# A-3_sch_class.net
KiCad netlist of a schematic drawn in EAGLE
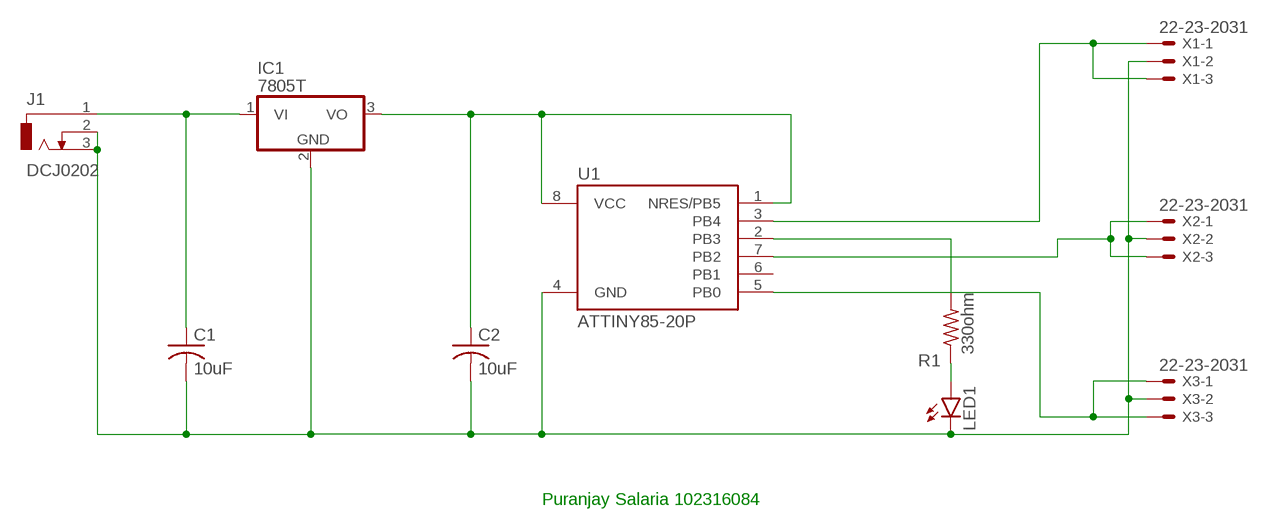
[diagram p0: schematic, sheet 1]

(export (version "E")
  (design (tool "Eeschema 10.0.6"))
  (components
    (comp (ref "C1")
      (value "10uF")
      (footprint "eagle-import:C025-024X044")
      (libsource (lib "eagle-import") (part "C-US025-024X044"))
    )
    (comp (ref "C2")
      (value "10uF")
      (footprint "eagle-import:C025-024X044")
      (libsource (lib "eagle-import") (part "C-US025-024X044"))
    )
    (comp (ref "IC1")
      (value "7805T")
      (footprint "eagle-import:TO220H")
      (libsource (lib "eagle-import") (part "78T05"))
    )
    (comp (ref "J1")
      (value "DCJ0202")
      (footprint "eagle-import:DCJ0202")
      (libsource (lib "eagle-import") (part "DCJ0202"))
    )
    (comp (ref "LED1")
      (value "LED3MM")
      (footprint "eagle-import:LED3MM")
      (libsource (lib "eagle-import") (part "LED3MM"))
    )
    (comp (ref "R1")
      (value "330ohm")
      (footprint "eagle-import:0207_5V")
      (libsource (lib "eagle-import") (part "R-US_0207/5V"))
    )
    (comp (ref "U1")
      (value "ATTINY85-20P")
      (footprint "eagle-import:PDIP08_300MIL")
      (libsource (lib "eagle-import") (part "ATTINY85P-20"))
    )
    (comp (ref "X1")
      (value "22-23-2031")
      (footprint "eagle-import:22-23-2031")
      (fields (field (name "MF") "MOLEX"))
      (libsource (lib "eagle-import") (part "22-23-2031"))
    )
    (comp (ref "X2")
      (value "22-23-2031")
      (footprint "eagle-import:22-23-2031")
      (fields (field (name "MF") "MOLEX"))
      (libsource (lib "eagle-import") (part "22-23-2031"))
    )
    (comp (ref "X3")
      (value "22-23-2031")
      (footprint "eagle-import:22-23-2031")
      (fields (field (name "MF") "MOLEX"))
      (libsource (lib "eagle-import") (part "22-23-2031"))
    )
  )
  (nets
    (net (code "1") (name "Net-(IC1-GND)") (class "Default")
      (node (ref "C1") (pin "2") (pinfunction "2_2") (pintype "passive"))
      (node (ref "C2") (pin "2") (pinfunction "2_2") (pintype "passive"))
      (node (ref "IC1") (pin "2") (pinfunction "GND_2") (pintype "passive"))
      (node (ref "J1") (pin "2") (pinfunction "2_2") (pintype "passive"))
      (node (ref "J1") (pin "3") (pinfunction "3_3") (pintype "passive"))
      (node (ref "LED1") (pin "K") (pinfunction "C_K") (pintype "passive"))
      (node (ref "U1") (pin "4") (pinfunction "GND_4") (pintype "power_in"))
      (node (ref "X1") (pin "2") (pinfunction "S_2") (pintype "passive"))
      (node (ref "X2") (pin "2") (pinfunction "S_2") (pintype "passive"))
      (node (ref "X3") (pin "2") (pinfunction "S_2") (pintype "passive"))
    )
    (net (code "2") (name "Net-(IC1-VI)") (class "Default")
      (node (ref "C1") (pin "1") (pinfunction "1_1") (pintype "passive"))
      (node (ref "IC1") (pin "1") (pinfunction "VI_1") (pintype "input"))
      (node (ref "J1") (pin "1") (pinfunction "1_1") (pintype "passive"))
    )
    (net (code "3") (name "Net-(IC1-VO)") (class "Default")
      (node (ref "C2") (pin "1") (pinfunction "1_1") (pintype "passive"))
      (node (ref "IC1") (pin "3") (pinfunction "VO_3") (pintype "passive"))
      (node (ref "U1") (pin "1") (pinfunction "NRES/PB5_1") (pintype "bidirectional"))
      (node (ref "U1") (pin "8") (pinfunction "VCC_8") (pintype "power_in"))
    )
    (net (code "4") (name "Net-(LED1-PadA)") (class "Default")
      (node (ref "LED1") (pin "A") (pinfunction "A_A") (pintype "passive"))
      (node (ref "R1") (pin "1") (pinfunction "1_1") (pintype "passive"))
    )
    (net (code "5") (name "Net-(U1-PB0)") (class "Default")
      (node (ref "U1") (pin "5") (pinfunction "PB0_5") (pintype "bidirectional"))
      (node (ref "X3") (pin "1") (pinfunction "S_1") (pintype "passive"))
      (node (ref "X3") (pin "3") (pinfunction "S_3") (pintype "passive"))
    )
    (net (code "6") (name "Net-(U1-PB2)") (class "Default")
      (node (ref "U1") (pin "7") (pinfunction "PB2_7") (pintype "bidirectional"))
      (node (ref "X2") (pin "1") (pinfunction "S_1") (pintype "passive"))
      (node (ref "X2") (pin "3") (pinfunction "S_3") (pintype "passive"))
    )
    (net (code "7") (name "Net-(U1-PB3)") (class "Default")
      (node (ref "R1") (pin "2") (pinfunction "2_2") (pintype "passive"))
      (node (ref "U1") (pin "2") (pinfunction "PB3_2") (pintype "bidirectional"))
    )
    (net (code "8") (name "Net-(U1-PB4)") (class "Default")
      (node (ref "U1") (pin "3") (pinfunction "PB4_3") (pintype "bidirectional"))
      (node (ref "X1") (pin "1") (pinfunction "S_1") (pintype "passive"))
      (node (ref "X1") (pin "3") (pinfunction "S_3") (pintype "passive"))
    )
    (net (code "9") (name "unconnected-(U1-PB1-Pad6)") (class "Default")
      (node (ref "U1") (pin "6") (pinfunction "PB1_6") (pintype "bidirectional"))
    )
  )
)
